# Test.net
KiCad netlist of a schematic drawn in Altium Designer
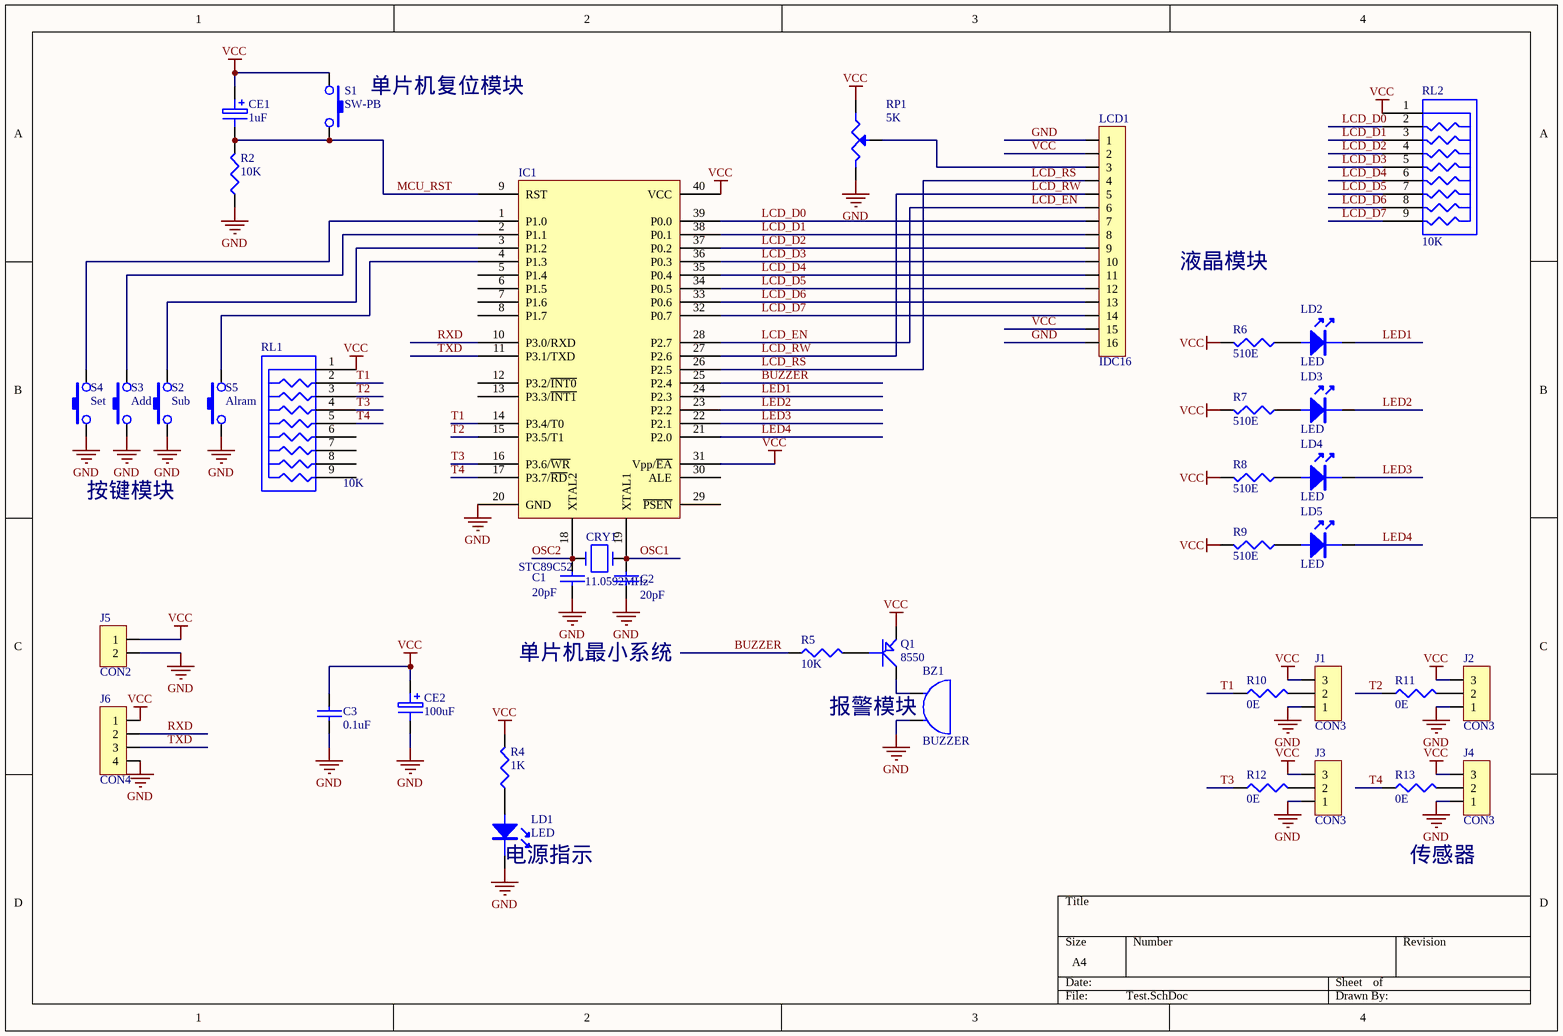
[diagram p0: Test.SchDoc]

(export (version "E")
  (design (tool "Eeschema 10.0.6"))
  (components
    (comp (ref "BZ1") (value "BUZZER") (footprint "BUZZER1") (libsource (lib "Sch1") (part "BUZZER")))
    (comp (ref "C1")
      (value "20pF")
      (footprint "RAD0.1")
      (description "Capacitor")
      (libsource (lib "*") (part "CAP"))
    )
    (comp (ref "C2")
      (value "20pF")
      (footprint "RAD0.1")
      (description "Capacitor")
      (libsource (lib "*") (part "CAP"))
    )
    (comp (ref "C3") (value "0.1uF") (footprint "RAD0.1") (libsource (lib "Sch1") (part "CAP")))
    (comp (ref "CE1") (value "1uF") (footprint "RB.1/.1L") (libsource (lib "Sch1") (part "ELECTRO1")))
    (comp (ref "CE2") (value "100uF") (footprint "RB.1/.2") (libsource (lib "Sch1") (part "ELECTRO1")))
    (comp (ref "CRY1") (value "11.0592MHz") (footprint "XTAL1") (libsource (lib "*") (part "CRYSTAL")))
    (comp (ref "IC1") (value "STC89C52") (footprint "DIP40") (libsource (lib "Sch") (part "AT89C51")))
    (comp (ref "J1") (value "CON3") (footprint "HJ3P2.54") (libsource (lib "Sch1") (part "CON3")))
    (comp (ref "J2") (value "CON3") (footprint "HJ3P2.54") (libsource (lib "Sch1") (part "CON3")))
    (comp (ref "J3") (value "CON3") (footprint "HJ3P2.54") (libsource (lib "Sch1") (part "CON3")))
    (comp (ref "J4") (value "CON3") (footprint "HJ3P2.54") (libsource (lib "Sch1") (part "CON3")))
    (comp (ref "J5") (value "CON2") (footprint "HJ2P2.54") (libsource (lib "Sch1") (part "CON2")))
    (comp (ref "J6") (value "CON4") (footprint "HJ4P2.54") (libsource (lib "Sch1") (part "CON4")))
    (comp (ref "LCD1") (value "IDC16") (footprint "LCD1602A") (libsource (lib "Sch1") (part "CON16")))
    (comp (ref "LD1") (value "LED") (footprint "LEDF3") (libsource (lib "Sch1") (part "LED")))
    (comp (ref "LD2") (value "LED") (footprint "LEDF3") (libsource (lib "Sch1") (part "LED")))
    (comp (ref "LD3") (value "LED") (footprint "LEDF3") (libsource (lib "Sch1") (part "LED")))
    (comp (ref "LD4") (value "LED") (footprint "LEDF3") (libsource (lib "Sch1") (part "LED")))
    (comp (ref "LD5") (value "LED") (footprint "LEDF3") (libsource (lib "Sch1") (part "LED")))
    (comp (ref "Q1") (value "8550") (footprint "TR-EBC") (libsource (lib "Sch1") (part "PNP1")))
    (comp (ref "R2") (value "10K") (footprint "AXIAL0.3") (libsource (lib "Sch1") (part "RES1")))
    (comp (ref "R4") (value "1K") (footprint "AXIAL0.3") (libsource (lib "Sch1") (part "RES1")))
    (comp (ref "R5") (value "10K") (footprint "AXIAL0.3") (libsource (lib "Sch1") (part "RES1")))
    (comp (ref "R6") (value "510E") (footprint "AXIAL0.3") (libsource (lib "Sch1") (part "RES1")))
    (comp (ref "R7") (value "510E") (footprint "AXIAL0.3") (libsource (lib "Sch1") (part "RES1")))
    (comp (ref "R8") (value "510E") (footprint "AXIAL0.3") (libsource (lib "Sch1") (part "RES1")))
    (comp (ref "R9") (value "510E") (footprint "AXIAL0.3") (libsource (lib "Sch1") (part "RES1")))
    (comp (ref "R10") (value "0E") (footprint "AXIAL0.3") (libsource (lib "Sch1") (part "RES1")))
    (comp (ref "R11") (value "0E") (footprint "AXIAL0.3") (libsource (lib "Sch1") (part "RES1")))
    (comp (ref "R12") (value "0E") (footprint "AXIAL0.3") (libsource (lib "Sch1") (part "RES1")))
    (comp (ref "R13") (value "0E") (footprint "AXIAL0.3") (libsource (lib "Sch1") (part "RES1")))
    (comp (ref "RL1") (value "10K") (footprint "RES9P") (libsource (lib "Sch1") (part "RESL1")))
    (comp (ref "RL2") (value "10K") (footprint "RES9P") (libsource (lib "Sch1") (part "RESL1")))
    (comp (ref "RP1") (value "5K") (footprint "WR1") (libsource (lib "Sch1") (part "POT1")))
    (comp (ref "S1") (value "SW-PB") (footprint "SW-PB4DS") (libsource (lib "Sch1") (part "SW-PB")))
    (comp (ref "S2") (value "Sub") (footprint "SW-PB4DS") (libsource (lib "Sch1") (part "SW-PB")))
    (comp (ref "S3") (value "Add") (footprint "SW-PB4DS") (libsource (lib "Sch1") (part "SW-PB")))
    (comp (ref "S4") (value "Set") (footprint "SW-PB4DS") (libsource (lib "Sch1") (part "SW-PB")))
    (comp (ref "S5") (value "Alram") (footprint "SW-PB4DS") (libsource (lib "Sch1") (part "SW-PB")))
  )
  (nets
    (net (code "1") (name "/BUZZER") (class "Default")
      (node (ref "IC1") (pin "25") (pinfunction "P2.4_25") (pintype "passive"))
      (node (ref "R5") (pin "1") (pintype "passive"))
    )
    (net (code "2") (name "/LCD_D0") (class "Default")
      (node (ref "IC1") (pin "39") (pinfunction "P0.0_39") (pintype "passive"))
      (node (ref "LCD1") (pin "7") (pinfunction "7_7") (pintype "passive"))
      (node (ref "RL2") (pin "2") (pinfunction "2_2") (pintype "passive"))
    )
    (net (code "3") (name "/LCD_D1") (class "Default")
      (node (ref "IC1") (pin "38") (pinfunction "P0.1_38") (pintype "passive"))
      (node (ref "LCD1") (pin "8") (pinfunction "8_8") (pintype "passive"))
      (node (ref "RL2") (pin "3") (pinfunction "3_3") (pintype "passive"))
    )
    (net (code "4") (name "/LCD_D2") (class "Default")
      (node (ref "IC1") (pin "37") (pinfunction "P0.2_37") (pintype "passive"))
      (node (ref "LCD1") (pin "9") (pinfunction "9_9") (pintype "passive"))
      (node (ref "RL2") (pin "4") (pinfunction "4_4") (pintype "passive"))
    )
    (net (code "5") (name "/LCD_D3") (class "Default")
      (node (ref "IC1") (pin "36") (pinfunction "P0.3_36") (pintype "passive"))
      (node (ref "LCD1") (pin "10") (pinfunction "10_10") (pintype "passive"))
      (node (ref "RL2") (pin "5") (pinfunction "5_5") (pintype "passive"))
    )
    (net (code "6") (name "/LCD_D4") (class "Default")
      (node (ref "IC1") (pin "35") (pinfunction "P0.4_35") (pintype "passive"))
      (node (ref "LCD1") (pin "11") (pinfunction "11_11") (pintype "passive"))
      (node (ref "RL2") (pin "6") (pinfunction "6_6") (pintype "passive"))
    )
    (net (code "7") (name "/LCD_D5") (class "Default")
      (node (ref "IC1") (pin "34") (pinfunction "P0.5_34") (pintype "passive"))
      (node (ref "LCD1") (pin "12") (pinfunction "12_12") (pintype "passive"))
      (node (ref "RL2") (pin "7") (pinfunction "7_7") (pintype "passive"))
    )
    (net (code "8") (name "/LCD_D6") (class "Default")
      (node (ref "IC1") (pin "33") (pinfunction "P0.6_33") (pintype "passive"))
      (node (ref "LCD1") (pin "13") (pinfunction "13_13") (pintype "passive"))
      (node (ref "RL2") (pin "8") (pinfunction "8_8") (pintype "passive"))
    )
    (net (code "9") (name "/LCD_D7") (class "Default")
      (node (ref "IC1") (pin "32") (pinfunction "P0.7_32") (pintype "passive"))
      (node (ref "LCD1") (pin "14") (pinfunction "14_14") (pintype "passive"))
      (node (ref "RL2") (pin "9") (pinfunction "9_9") (pintype "passive"))
    )
    (net (code "10") (name "/LCD_EN") (class "Default")
      (node (ref "IC1") (pin "28") (pinfunction "P2.7_28") (pintype "passive"))
      (node (ref "LCD1") (pin "6") (pinfunction "6_6") (pintype "passive"))
    )
    (net (code "11") (name "/LCD_RS") (class "Default")
      (node (ref "IC1") (pin "26") (pinfunction "P2.5_26") (pintype "passive"))
      (node (ref "LCD1") (pin "4") (pinfunction "4_4") (pintype "passive"))
    )
    (net (code "12") (name "/LCD_RW") (class "Default")
      (node (ref "IC1") (pin "27") (pinfunction "P2.6_27") (pintype "passive"))
      (node (ref "LCD1") (pin "5") (pinfunction "5_5") (pintype "passive"))
    )
    (net (code "13") (name "/LED1") (class "Default")
      (node (ref "IC1") (pin "24") (pinfunction "P2.3_24") (pintype "passive"))
      (node (ref "LD2") (pin "K") (pintype "passive"))
    )
    (net (code "14") (name "/LED2") (class "Default")
      (node (ref "IC1") (pin "23") (pinfunction "P2.2_23") (pintype "passive"))
      (node (ref "LD3") (pin "K") (pintype "passive"))
    )
    (net (code "15") (name "/LED3") (class "Default")
      (node (ref "IC1") (pin "22") (pinfunction "P2.1_22") (pintype "passive"))
      (node (ref "LD4") (pin "K") (pintype "passive"))
    )
    (net (code "16") (name "/LED4") (class "Default")
      (node (ref "IC1") (pin "21") (pinfunction "P2.0_21") (pintype "passive"))
      (node (ref "LD5") (pin "K") (pintype "passive"))
    )
    (net (code "17") (name "/MCU_RST") (class "Default")
      (node (ref "CE1") (pin "2") (pintype "passive"))
      (node (ref "IC1") (pin "9") (pinfunction "RST_9") (pintype "passive"))
      (node (ref "R2") (pin "2") (pintype "passive"))
      (node (ref "S1") (pin "2") (pintype "passive"))
    )
    (net (code "18") (name "/OSC1") (class "Default")
      (node (ref "C2") (pin "1") (pinfunction "1_1") (pintype "passive"))
      (node (ref "CRY1") (pin "2") (pinfunction "2_2") (pintype "passive"))
      (node (ref "IC1") (pin "19") (pinfunction "XTAL1_19") (pintype "passive"))
    )
    (net (code "19") (name "/OSC2") (class "Default")
      (node (ref "C1") (pin "1") (pinfunction "1_1") (pintype "passive"))
      (node (ref "CRY1") (pin "1") (pinfunction "1_1") (pintype "passive"))
      (node (ref "IC1") (pin "18") (pinfunction "XTAL2_18") (pintype "passive"))
    )
    (net (code "20") (name "/RXD") (class "Default")
      (node (ref "IC1") (pin "10") (pinfunction "P3.0/RXD_10") (pintype "passive"))
      (node (ref "J6") (pin "2") (pinfunction "2_2") (pintype "passive"))
    )
    (net (code "21") (name "/T1") (class "Default")
      (node (ref "IC1") (pin "14") (pinfunction "P3.4/T0_14") (pintype "passive"))
      (node (ref "R10") (pin "1") (pintype "passive"))
      (node (ref "RL1") (pin "2") (pinfunction "2_2") (pintype "passive"))
    )
    (net (code "22") (name "/T2") (class "Default")
      (node (ref "IC1") (pin "15") (pinfunction "P3.5/T1_15") (pintype "passive"))
      (node (ref "R11") (pin "1") (pintype "passive"))
      (node (ref "RL1") (pin "3") (pinfunction "3_3") (pintype "passive"))
    )
    (net (code "23") (name "/T3") (class "Default")
      (node (ref "IC1") (pin "16") (pinfunction "P3.6/~{WR}_16") (pintype "passive"))
      (node (ref "R12") (pin "1") (pintype "passive"))
      (node (ref "RL1") (pin "4") (pinfunction "4_4") (pintype "passive"))
    )
    (net (code "24") (name "/T4") (class "Default")
      (node (ref "IC1") (pin "17") (pinfunction "P3.7/~{RD}_17") (pintype "passive"))
      (node (ref "R13") (pin "1") (pintype "passive"))
      (node (ref "RL1") (pin "5") (pinfunction "5_5") (pintype "passive"))
    )
    (net (code "25") (name "/TXD") (class "Default")
      (node (ref "IC1") (pin "11") (pinfunction "P3.1/TXD_11") (pintype "passive"))
      (node (ref "J6") (pin "3") (pinfunction "3_3") (pintype "passive"))
    )
    (net (code "26") (name "GND") (class "Default")
      (node (ref "BZ1") (pin "2") (pintype "passive"))
      (node (ref "C1") (pin "2") (pinfunction "2_2") (pintype "passive"))
      (node (ref "C2") (pin "2") (pinfunction "2_2") (pintype "passive"))
      (node (ref "C3") (pin "2") (pintype "passive"))
      (node (ref "CE2") (pin "2") (pintype "passive"))
      (node (ref "IC1") (pin "20") (pinfunction "GND_20") (pintype "passive"))
      (node (ref "J1") (pin "1") (pinfunction "1_1") (pintype "passive"))
      (node (ref "J2") (pin "1") (pinfunction "1_1") (pintype "passive"))
      (node (ref "J3") (pin "1") (pinfunction "1_1") (pintype "passive"))
      (node (ref "J4") (pin "1") (pinfunction "1_1") (pintype "passive"))
      (node (ref "J5") (pin "2") (pinfunction "2_2") (pintype "passive"))
      (node (ref "J6") (pin "4") (pinfunction "4_4") (pintype "passive"))
      (node (ref "LCD1") (pin "1") (pinfunction "1_1") (pintype "passive"))
      (node (ref "LCD1") (pin "16") (pinfunction "16_16") (pintype "passive"))
      (node (ref "LD1") (pin "K") (pintype "passive"))
      (node (ref "R2") (pin "1") (pintype "passive"))
      (node (ref "RP1") (pin "1") (pintype "passive"))
      (node (ref "S2") (pin "2") (pintype "passive"))
      (node (ref "S3") (pin "2") (pintype "passive"))
      (node (ref "S4") (pin "2") (pintype "passive"))
      (node (ref "S5") (pin "2") (pintype "passive"))
    )
    (net (code "27") (name "Net-(BZ1-Pad1)") (class "Default")
      (node (ref "BZ1") (pin "1") (pintype "passive"))
      (node (ref "Q1") (pin "COLL") (pinfunction "COLL_COLL") (pintype "passive"))
    )
    (net (code "28") (name "Net-(IC1-P1.0)") (class "Default")
      (node (ref "IC1") (pin "1") (pinfunction "P1.0_1") (pintype "passive"))
      (node (ref "S4") (pin "1") (pintype "passive"))
    )
    (net (code "29") (name "Net-(IC1-P1.1)") (class "Default")
      (node (ref "IC1") (pin "2") (pinfunction "P1.1_2") (pintype "passive"))
      (node (ref "S3") (pin "1") (pintype "passive"))
    )
    (net (code "30") (name "Net-(IC1-P1.2)") (class "Default")
      (node (ref "IC1") (pin "3") (pinfunction "P1.2_3") (pintype "passive"))
      (node (ref "S2") (pin "1") (pintype "passive"))
    )
    (net (code "31") (name "Net-(IC1-P1.3)") (class "Default")
      (node (ref "IC1") (pin "4") (pinfunction "P1.3_4") (pintype "passive"))
      (node (ref "S5") (pin "1") (pintype "passive"))
    )
    (net (code "32") (name "Net-(J1-Pad2)") (class "Default")
      (node (ref "J1") (pin "2") (pinfunction "2_2") (pintype "passive"))
      (node (ref "R10") (pin "2") (pintype "passive"))
    )
    (net (code "33") (name "Net-(J2-Pad2)") (class "Default")
      (node (ref "J2") (pin "2") (pinfunction "2_2") (pintype "passive"))
      (node (ref "R11") (pin "2") (pintype "passive"))
    )
    (net (code "34") (name "Net-(J3-Pad2)") (class "Default")
      (node (ref "J3") (pin "2") (pinfunction "2_2") (pintype "passive"))
      (node (ref "R12") (pin "2") (pintype "passive"))
    )
    (net (code "35") (name "Net-(J4-Pad2)") (class "Default")
      (node (ref "J4") (pin "2") (pinfunction "2_2") (pintype "passive"))
      (node (ref "R13") (pin "2") (pintype "passive"))
    )
    (net (code "36") (name "Net-(LCD1-Pad3)") (class "Default")
      (node (ref "LCD1") (pin "3") (pinfunction "3_3") (pintype "passive"))
      (node (ref "RP1") (pin "W") (pintype "passive"))
    )
    (net (code "37") (name "Net-(LD1-PadA)") (class "Default")
      (node (ref "LD1") (pin "A") (pintype "passive"))
      (node (ref "R4") (pin "1") (pintype "passive"))
    )
    (net (code "38") (name "Net-(LD2-PadA)") (class "Default")
      (node (ref "LD2") (pin "A") (pintype "passive"))
      (node (ref "R6") (pin "1") (pintype "passive"))
    )
    (net (code "39") (name "Net-(LD3-PadA)") (class "Default")
      (node (ref "LD3") (pin "A") (pintype "passive"))
      (node (ref "R7") (pin "1") (pintype "passive"))
    )
    (net (code "40") (name "Net-(LD4-PadA)") (class "Default")
      (node (ref "LD4") (pin "A") (pintype "passive"))
      (node (ref "R8") (pin "1") (pintype "passive"))
    )
    (net (code "41") (name "Net-(LD5-PadA)") (class "Default")
      (node (ref "LD5") (pin "A") (pintype "passive"))
      (node (ref "R9") (pin "1") (pintype "passive"))
    )
    (net (code "42") (name "Net-(Q1-PadBASE)") (class "Default")
      (node (ref "Q1") (pin "BASE") (pinfunction "BASE_BASE") (pintype "passive"))
      (node (ref "R5") (pin "2") (pintype "passive"))
    )
    (net (code "43") (name "VCC") (class "Default")
      (node (ref "C3") (pin "1") (pintype "passive"))
      (node (ref "CE1") (pin "1") (pintype "passive"))
      (node (ref "CE2") (pin "1") (pintype "passive"))
      (node (ref "IC1") (pin "31") (pinfunction "Vpp/~{EA}_31") (pintype "passive"))
      (node (ref "IC1") (pin "40") (pinfunction "VCC_40") (pintype "passive"))
      (node (ref "J1") (pin "3") (pinfunction "3_3") (pintype "passive"))
      (node (ref "J2") (pin "3") (pinfunction "3_3") (pintype "passive"))
      (node (ref "J3") (pin "3") (pinfunction "3_3") (pintype "passive"))
      (node (ref "J4") (pin "3") (pinfunction "3_3") (pintype "passive"))
      (node (ref "J5") (pin "1") (pinfunction "1_1") (pintype "passive"))
      (node (ref "J6") (pin "1") (pinfunction "1_1") (pintype "passive"))
      (node (ref "LCD1") (pin "15") (pinfunction "15_15") (pintype "passive"))
      (node (ref "LCD1") (pin "2") (pinfunction "2_2") (pintype "passive"))
      (node (ref "Q1") (pin "EMIT") (pinfunction "EMIT_EMIT") (pintype "passive"))
      (node (ref "R4") (pin "2") (pintype "passive"))
      (node (ref "R6") (pin "2") (pintype "passive"))
      (node (ref "R7") (pin "2") (pintype "passive"))
      (node (ref "R8") (pin "2") (pintype "passive"))
      (node (ref "R9") (pin "2") (pintype "passive"))
      (node (ref "RL1") (pin "1") (pinfunction "1_1") (pintype "passive"))
      (node (ref "RL2") (pin "1") (pinfunction "1_1") (pintype "passive"))
      (node (ref "RP1") (pin "2") (pintype "passive"))
      (node (ref "S1") (pin "1") (pintype "passive"))
    )
    (net (code "44") (name "unconnected-(IC1-ALE-Pad30)") (class "Default")
      (node (ref "IC1") (pin "30") (pinfunction "ALE_30") (pintype "passive"))
    )
    (net (code "45") (name "unconnected-(IC1-P1.4-Pad5)") (class "Default")
      (node (ref "IC1") (pin "5") (pinfunction "P1.4_5") (pintype "passive"))
    )
    (net (code "46") (name "unconnected-(IC1-P1.5-Pad6)") (class "Default")
      (node (ref "IC1") (pin "6") (pinfunction "P1.5_6") (pintype "passive"))
    )
    (net (code "47") (name "unconnected-(IC1-P1.6-Pad7)") (class "Default")
      (node (ref "IC1") (pin "7") (pinfunction "P1.6_7") (pintype "passive"))
    )
    (net (code "48") (name "unconnected-(IC1-P1.7-Pad8)") (class "Default")
      (node (ref "IC1") (pin "8") (pinfunction "P1.7_8") (pintype "passive"))
    )
    (net (code "49") (name "unconnected-(IC1-P3.2{slash}~{INT0}-Pad12)") (class "Default")
      (node (ref "IC1") (pin "12") (pinfunction "P3.2/~{INT0}_12") (pintype "passive"))
    )
    (net (code "50") (name "unconnected-(IC1-P3.3{slash}~{INT1}-Pad13)") (class "Default")
      (node (ref "IC1") (pin "13") (pinfunction "P3.3/~{INT1}_13") (pintype "passive"))
    )
    (net (code "51") (name "unconnected-(IC1-~{PSEN}-Pad29)") (class "Default")
      (node (ref "IC1") (pin "29") (pinfunction "~{PSEN}_29") (pintype "passive"))
    )
    (net (code "52") (name "unconnected-(RL1-Pad6)") (class "Default")
      (node (ref "RL1") (pin "6") (pinfunction "6_6") (pintype "passive"))
    )
    (net (code "53") (name "unconnected-(RL1-Pad7)") (class "Default")
      (node (ref "RL1") (pin "7") (pinfunction "7_7") (pintype "passive"))
    )
    (net (code "54") (name "unconnected-(RL1-Pad8)") (class "Default")
      (node (ref "RL1") (pin "8") (pinfunction "8_8") (pintype "passive"))
    )
    (net (code "55") (name "unconnected-(RL1-Pad9)") (class "Default")
      (node (ref "RL1") (pin "9") (pinfunction "9_9") (pintype "passive"))
    )
  )
)
